# design.net
KiCad netlist of a schematic drawn in Altium Designer
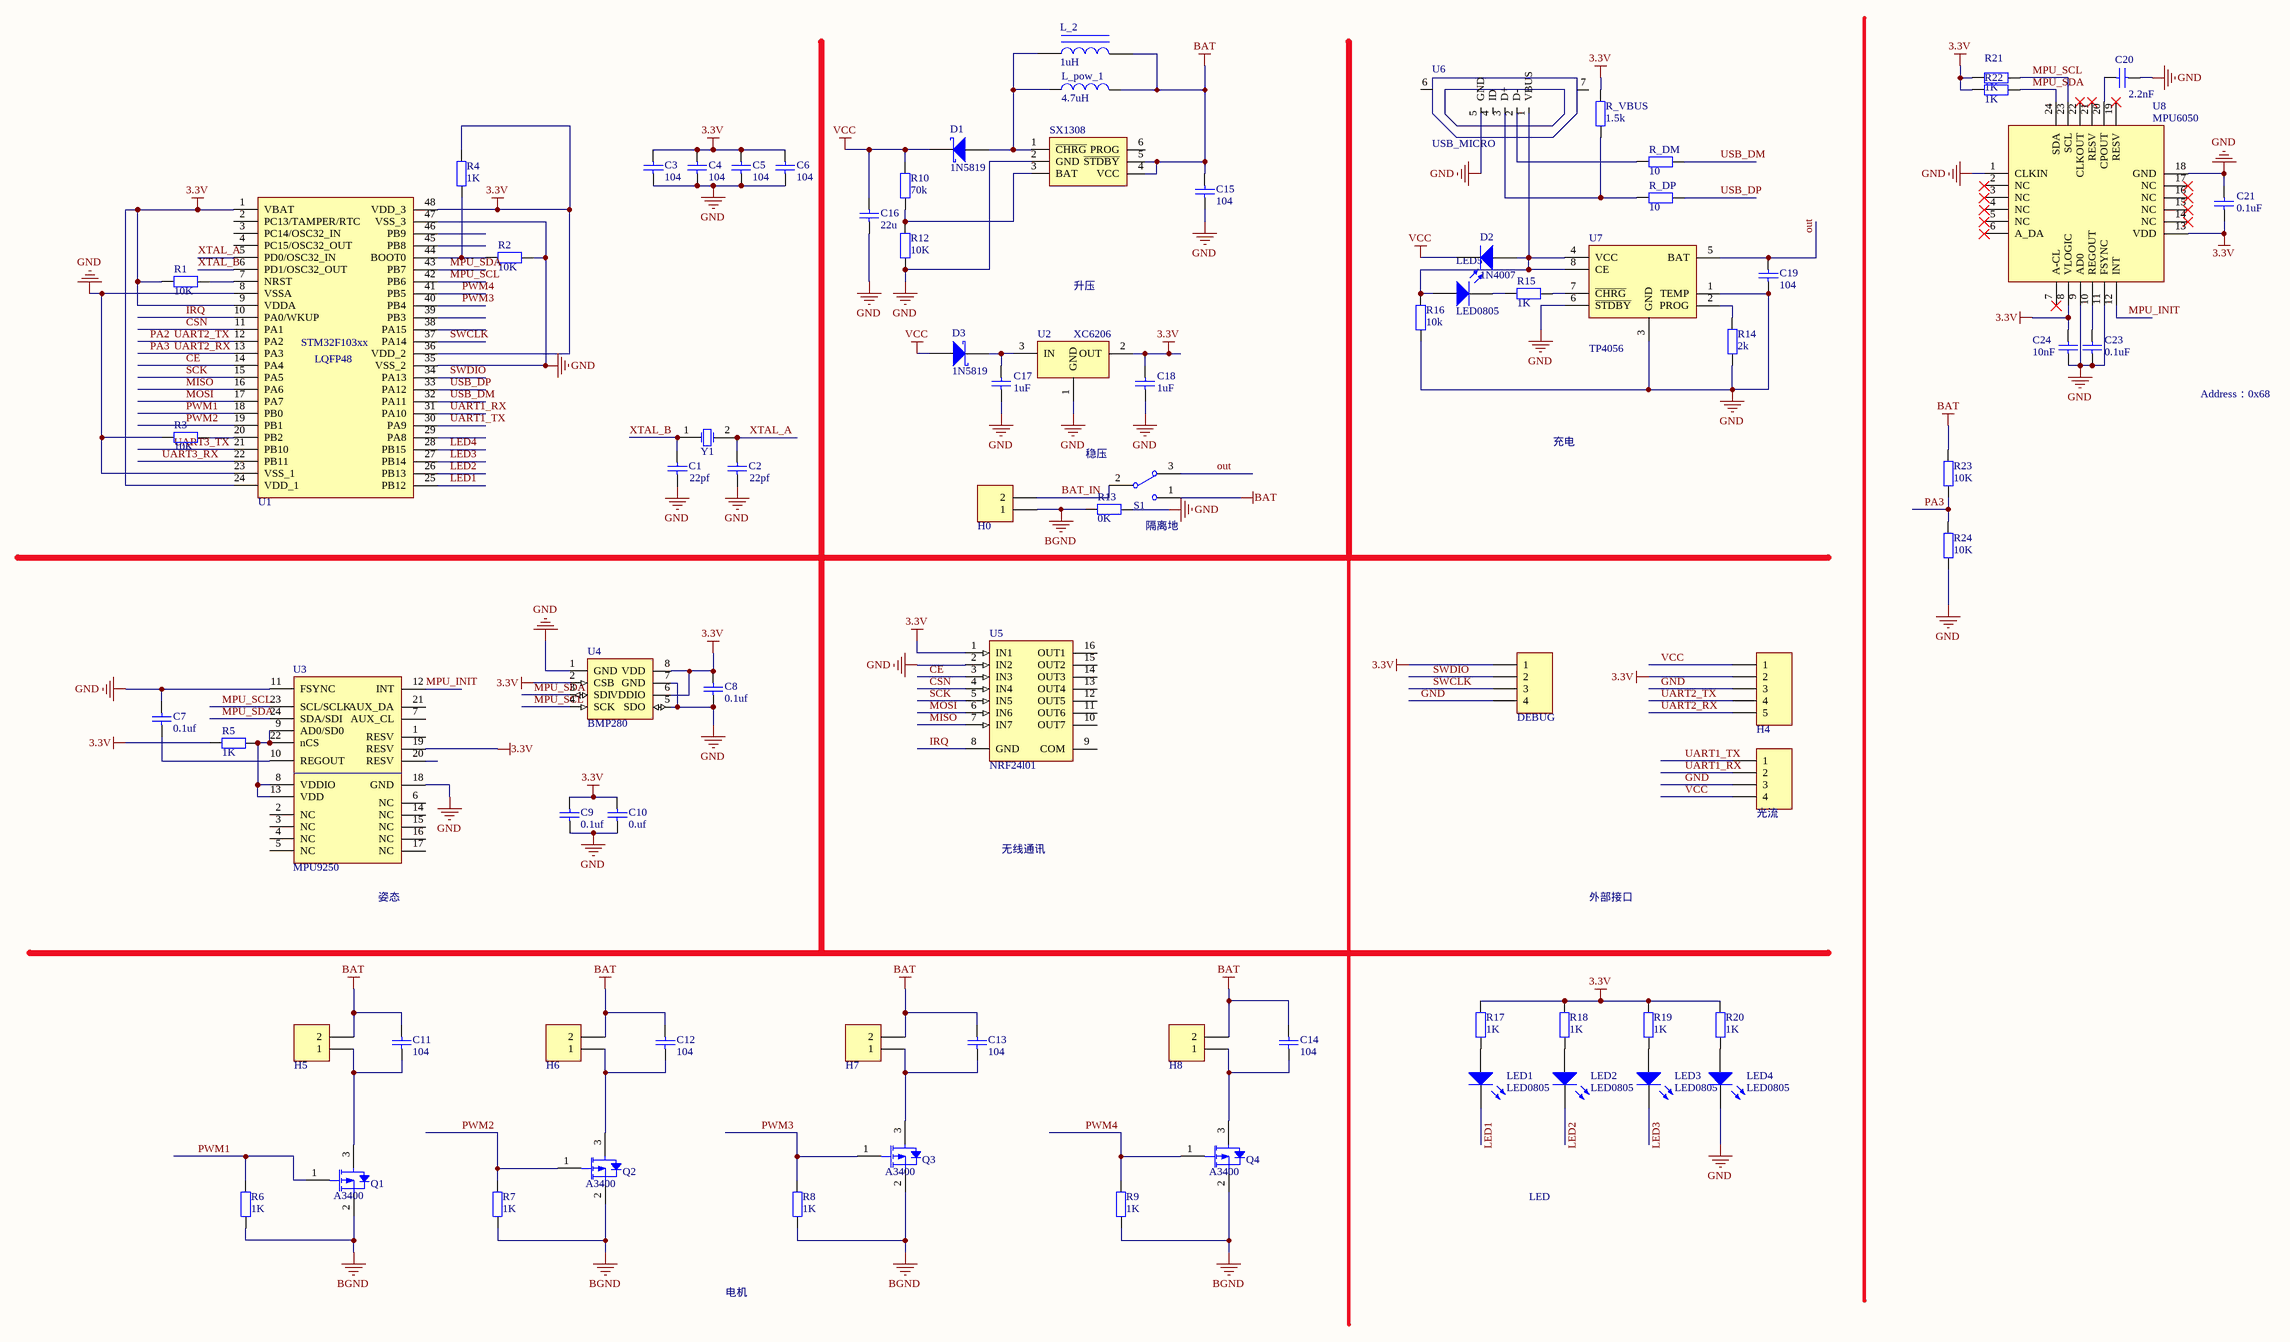
[diagram p0: 小四轴.SchDoc]

(export (version "E")
  (design (tool "Eeschema 10.0.6"))
  (components
    (comp (ref "C1")
      (value "22")
      (footprint "0603C")
      (description "0603瓷片电容")
      (fields (field (name "ALTIUM_UNNAMED_1") "22pf"))
      (libsource (lib "0.电阻电容电感") (part "Cap_0603"))
    )
    (comp (ref "C2")
      (value "104")
      (footprint "0603C")
      (description "0603瓷片电容")
      (fields (field (name "ALTIUM_UNNAMED_1") "22pf"))
      (libsource (lib "0.电阻电容电感") (part "Cap_0603"))
    )
    (comp (ref "C3")
      (value "104")
      (footprint "0603C")
      (description "0603瓷片电容")
      (libsource (lib "0.电阻电容电感") (part "Cap_0603"))
    )
    (comp (ref "C4")
      (value "104")
      (footprint "0603C")
      (description "0603瓷片电容")
      (libsource (lib "0.电阻电容电感") (part "Cap_0603"))
    )
    (comp (ref "C5")
      (value "104")
      (footprint "0603C")
      (description "0603瓷片电容")
      (libsource (lib "0.电阻电容电感") (part "Cap_0603"))
    )
    (comp (ref "C6")
      (value "104")
      (footprint "0603C")
      (description "0603瓷片电容")
      (libsource (lib "0.电阻电容电感") (part "Cap_0603"))
    )
    (comp (ref "C7")
      (value "0.1uf")
      (footprint "0603C")
      (description "0603瓷片电容")
      (libsource (lib "0.电阻电容电感") (part "Cap_0603"))
    )
    (comp (ref "C8")
      (value "0.1uf")
      (footprint "0603C")
      (description "0603瓷片电容")
      (libsource (lib "0.电阻电容电感") (part "Cap_0603"))
    )
    (comp (ref "C9")
      (value "0.1uf")
      (footprint "0603C")
      (description "0603瓷片电容")
      (libsource (lib "0.电阻电容电感") (part "Cap_0603"))
    )
    (comp (ref "C10")
      (value "0.uf")
      (footprint "0603C")
      (description "0603瓷片电容")
      (libsource (lib "0.电阻电容电感") (part "Cap_0603"))
    )
    (comp (ref "C11")
      (value "104")
      (footprint "0603C")
      (description "0603瓷片电容")
      (libsource (lib "0.电阻电容电感") (part "Cap_0603"))
    )
    (comp (ref "C12")
      (value "104")
      (footprint "0603C")
      (description "0603瓷片电容")
      (libsource (lib "0.电阻电容电感") (part "Cap_0603"))
    )
    (comp (ref "C13")
      (value "104")
      (footprint "0603C")
      (description "0603瓷片电容")
      (libsource (lib "0.电阻电容电感") (part "Cap_0603"))
    )
    (comp (ref "C14")
      (value "104")
      (footprint "0603C")
      (description "0603瓷片电容")
      (libsource (lib "0.电阻电容电感") (part "Cap_0603"))
    )
    (comp (ref "C15")
      (value "104")
      (footprint "0603C")
      (description "0603瓷片电容")
      (libsource (lib "0.电阻电容电感") (part "Cap_0603"))
    )
    (comp (ref "C16")
      (value "22u")
      (footprint "0603C")
      (description "0603瓷片电容")
      (libsource (lib "0.电阻电容电感") (part "Cap_0603"))
    )
    (comp (ref "C17")
      (value "1uF")
      (footprint "C_0603")
      (fields (field (name "Comment") "C_0603") (field (name "PUBLISHER") "Altium Limited"))
      (libsource (lib "RoboFly") (part "C_0603"))
    )
    (comp (ref "C18")
      (value "1uF")
      (footprint "C_0603")
      (fields (field (name "Comment") "C_0603") (field (name "PUBLISHER") "Altium Limited"))
      (libsource (lib "RoboFly") (part "C_0603"))
    )
    (comp (ref "C19")
      (value "104")
      (footprint "0603C")
      (description "0603瓷片电容")
      (libsource (lib "0.电阻电容电感") (part "Cap_0603"))
    )
    (comp (ref "C20")
      (value "2.2nF")
      (footprint "C_0603")
      (fields (field (name "Comment") "C_0603") (field (name "PUBLISHER") "Altium Limited"))
      (libsource (lib "RoboFly") (part "C_0603"))
    )
    (comp (ref "C21")
      (value "0.1uF")
      (footprint "C_0603")
      (fields (field (name "Comment") "C_0603") (field (name "PUBLISHER") "Altium Limited"))
      (libsource (lib "RoboFly") (part "C_0603"))
    )
    (comp (ref "C23")
      (value "0.1uF")
      (footprint "C_0603")
      (fields (field (name "Comment") "C_0603") (field (name "PUBLISHER") "Altium Limited"))
      (libsource (lib "RoboFly") (part "C_0603"))
    )
    (comp (ref "C24")
      (value "10nF")
      (footprint "C_0603")
      (fields (field (name "Comment") "C_0603") (field (name "PUBLISHER") "Altium Limited"))
      (libsource (lib "RoboFly") (part "C_0603"))
    )
    (comp (ref "D1")
      (value "1N5819")
      (footprint "DO214AC_SMA")
      (description "贴片肖特基二极管")
      (libsource (lib "1.二极管") (part "1N5817-5819SMD"))
    )
    (comp (ref "D2")
      (value "1N4007")
      (footprint "DO214AC_SMA")
      (description "贴片整流二极管")
      (libsource (lib "1.二极管") (part "1N4001-4007SMD"))
    )
    (comp (ref "D3")
      (value "1N5819")
      (footprint "DO214AC_SMA")
      (description "贴片肖特基二极管")
      (libsource (lib "1.二极管") (part "1N5817-5819SMD"))
    )
    (comp (ref "H0")
      (value "Header 2")
      (footprint "HDR1X2")
      (description "Header, 2-Pin")
      (fields (field (name "PUBLISHER") "Altium Limited"))
      (libsource (lib "9.接插件 连接器") (part "Header 2"))
    )
    (comp (ref "H1")
      (value "DEBUG")
      (footprint "HDR1X4")
      (description "Header, 4-Pin")
      (fields (field (name "PUBLISHER") "Altium Limited"))
      (libsource (lib "9.接插件 连接器") (part "Header 4"))
    )
    (comp (ref "H3")
      (value "光流")
      (footprint "HDR1X4")
      (description "Header, 4-Pin")
      (fields (field (name "PUBLISHER") "Altium Limited"))
      (libsource (lib "9.接插件 连接器") (part "Header 4"))
    )
    (comp (ref "H4")
      (value "Header 5")
      (footprint "HDR1X5")
      (description "Header, 5-Pin")
      (fields (field (name "PUBLISHER") "Altium Limited"))
      (libsource (lib "9.接插件 连接器") (part "Header 5"))
    )
    (comp (ref "H5")
      (value "Header 2")
      (footprint "HDR1X2")
      (description "Header, 2-Pin")
      (fields (field (name "PUBLISHER") "Altium Limited"))
      (libsource (lib "9.接插件 连接器") (part "Header 2"))
    )
    (comp (ref "H6")
      (value "Header 2")
      (footprint "HDR1X2")
      (description "Header, 2-Pin")
      (fields (field (name "PUBLISHER") "Altium Limited"))
      (libsource (lib "9.接插件 连接器") (part "Header 2"))
    )
    (comp (ref "H7")
      (value "Header 2")
      (footprint "HDR1X2")
      (description "Header, 2-Pin")
      (fields (field (name "PUBLISHER") "Altium Limited"))
      (libsource (lib "9.接插件 连接器") (part "Header 2"))
    )
    (comp (ref "H8")
      (value "Header 2")
      (footprint "HDR1X2")
      (description "Header, 2-Pin")
      (fields (field (name "PUBLISHER") "Altium Limited"))
      (libsource (lib "9.接插件 连接器") (part "Header 2"))
    )
    (comp (ref "LED1") (value "LED0805") (footprint "LED-0805") (libsource (lib "1.二极管") (part "LED0805")))
    (comp (ref "LED2") (value "LED0805") (footprint "LED-0805") (libsource (lib "1.二极管") (part "LED0805")))
    (comp (ref "LED3") (value "LED0805") (footprint "LED-0805") (libsource (lib "1.二极管") (part "LED0805")))
    (comp (ref "LED4") (value "LED0805") (footprint "LED-0805") (libsource (lib "1.二极管") (part "LED0805")))
    (comp (ref "LED5") (value "LED0805") (footprint "LED-0805") (libsource (lib "1.二极管") (part "LED0805")))
    (comp (ref "L_2")
      (value "1uH")
      (footprint "IND5X4")
      (description "IND5X4")
      (libsource (lib "0.电阻电容电感") (part "L_IND5X4"))
    )
    (comp (ref "L_pow_1")
      (value "4.7uH")
      (footprint "0805L")
      (description "0805贴片电感")
      (libsource (lib "0.电阻电容电感") (part "L_0805"))
    )
    (comp (ref "Q1")
      (value "A3400")
      (footprint "SOT23")
      (description "P沟道增强型场效应管")
      (libsource (lib "2.晶体管") (part "P-MOS_SOT23"))
    )
    (comp (ref "Q2")
      (value "A3400")
      (footprint "SOT23")
      (description "P沟道增强型场效应管")
      (libsource (lib "2.晶体管") (part "P-MOS_SOT23"))
    )
    (comp (ref "Q3")
      (value "A3400")
      (footprint "SOT23")
      (description "P沟道增强型场效应管")
      (libsource (lib "2.晶体管") (part "P-MOS_SOT23"))
    )
    (comp (ref "Q4")
      (value "A3400")
      (footprint "SOT23")
      (description "P沟道增强型场效应管")
      (libsource (lib "2.晶体管") (part "P-MOS_SOT23"))
    )
    (comp (ref "R1")
      (value "10K")
      (footprint "0603R")
      (description "0603贴片电阻")
      (libsource (lib "0.电阻电容电感") (part "Res_0603"))
    )
    (comp (ref "R2")
      (value "10K")
      (footprint "0603R")
      (description "0603贴片电阻")
      (libsource (lib "0.电阻电容电感") (part "Res_0603"))
    )
    (comp (ref "R3")
      (value "10K")
      (footprint "0603R")
      (description "0603贴片电阻")
      (libsource (lib "0.电阻电容电感") (part "Res_0603"))
    )
    (comp (ref "R4")
      (value "1K")
      (footprint "0603R")
      (description "0603贴片电阻")
      (libsource (lib "") (part "Res_0603_1"))
    )
    (comp (ref "R5")
      (value "1K")
      (footprint "0603R")
      (description "0603贴片电阻")
      (libsource (lib "") (part "Res_0603_2"))
    )
    (comp (ref "R6")
      (value "1K")
      (footprint "0603R")
      (description "0603贴片电阻")
      (libsource (lib "") (part "Res_0603_3"))
    )
    (comp (ref "R7")
      (value "1K")
      (footprint "0603R")
      (description "0603贴片电阻")
      (libsource (lib "") (part "Res_0603_3"))
    )
    (comp (ref "R8")
      (value "1K")
      (footprint "0603R")
      (description "0603贴片电阻")
      (libsource (lib "") (part "Res_0603_3"))
    )
    (comp (ref "R9")
      (value "1K")
      (footprint "0603R")
      (description "0603贴片电阻")
      (libsource (lib "") (part "Res_0603_3"))
    )
    (comp (ref "R10")
      (value "70k")
      (footprint "0603R")
      (description "0603贴片电阻")
      (libsource (lib "") (part "Res_0603_1"))
    )
    (comp (ref "R12")
      (value "10K")
      (footprint "0603R")
      (description "0603贴片电阻")
      (libsource (lib "") (part "Res_0603_1"))
    )
    (comp (ref "R13")
      (value "0K")
      (footprint "0603R")
      (description "0603贴片电阻")
      (libsource (lib "0.电阻电容电感") (part "Res_0603"))
    )
    (comp (ref "R14")
      (value "2k")
      (footprint "0603R")
      (description "0603贴片电阻")
      (libsource (lib "") (part "Res_0603_3"))
    )
    (comp (ref "R15")
      (value "1K")
      (footprint "0603R")
      (description "0603贴片电阻")
      (libsource (lib "") (part "Res_0603_2"))
    )
    (comp (ref "R16")
      (value "10k")
      (footprint "0603R")
      (description "0603贴片电阻")
      (libsource (lib "") (part "Res_0603_3"))
    )
    (comp (ref "R17")
      (value "1K")
      (footprint "0805R")
      (description "0805贴片电阻")
      (libsource (lib "0.电阻电容电感") (part "Res_0805"))
    )
    (comp (ref "R18")
      (value "1K")
      (footprint "0805R")
      (description "0805贴片电阻")
      (libsource (lib "0.电阻电容电感") (part "Res_0805"))
    )
    (comp (ref "R19")
      (value "1K")
      (footprint "0805R")
      (description "0805贴片电阻")
      (libsource (lib "0.电阻电容电感") (part "Res_0805"))
    )
    (comp (ref "R20")
      (value "1K")
      (footprint "0805R")
      (description "0805贴片电阻")
      (libsource (lib "0.电阻电容电感") (part "Res_0805"))
    )
    (comp (ref "R21")
      (value "1K")
      (footprint "0603R")
      (description "0603贴片电阻")
      (libsource (lib "") (part "Res_0603_2"))
    )
    (comp (ref "R22")
      (value "1K")
      (footprint "0603R")
      (description "0603贴片电阻")
      (libsource (lib "") (part "Res_0603_2"))
    )
    (comp (ref "R23")
      (value "10K")
      (footprint "0603R")
      (description "0603贴片电阻")
      (libsource (lib "") (part "Res_0603_3"))
    )
    (comp (ref "R24")
      (value "10K")
      (footprint "0603R")
      (description "0603贴片电阻")
      (libsource (lib "") (part "Res_0603_3"))
    )
    (comp (ref "R_DM")
      (value "10")
      (footprint "0603R")
      (description "0603贴片电阻")
      (libsource (lib "0.电阻电容电感") (part "Res_0603"))
    )
    (comp (ref "R_DP")
      (value "10")
      (footprint "0603R")
      (description "0603贴片电阻")
      (libsource (lib "0.电阻电容电感") (part "Res_0603"))
    )
    (comp (ref "R_VBUS")
      (value "1.5k")
      (footprint "0603R")
      (description "0603贴片电阻")
      (libsource (lib "") (part "Res_0603_1"))
    )
    (comp (ref "S1")
      (value "2档平拨开关 无支撑")
      (footprint "平拨2档开关100mil")
      (description "2.54mm脚距 无支撑")
      (libsource (lib "6.开关 按键") (part "2档平拨开关 无支撑"))
    )
    (comp (ref "SX1308") (value "TP4059") (footprint "SOT23-6S") (libsource (lib "MiniFly+") (part "TP4059")))
    (comp (ref "U1")
      (value "STM32F103C8T6")
      (footprint "LQFP48_M")
      (libsource (lib "7.MCU CPU") (part "STM32F103C8T6"))
    )
    (comp (ref "U2")
      (value "XC6206")
      (footprint "SOT-23(SOT-23-3)")
      (fields (field (name "PUBLISHER") "mazhongwei"))
      (libsource (lib "RoboFly") (part "XC6206"))
    )
    (comp (ref "U3") (value "MPU9250") (footprint "QFN24-0.4") (libsource (lib "MiniFly+") (part "MPU9250")))
    (comp (ref "U4") (value "BMP280") (footprint "LGA-8") (libsource (lib "MiniFly+") (part "BMP280")))
    (comp (ref "U5")
      (value "NRF24l01")
      (footprint "NSO16_M")
      (description "驱动芯片")
      (fields (field (name "PUBLISHER") "Altium Limited"))
      (libsource (lib "Fszhang") (part "ULN2003L"))
    )
    (comp (ref "U6")
      (value "USB_MICRO")
      (footprint "USB micro")
      (libsource (lib "9.接插件 连接器") (part "USB_MICRO"))
    )
    (comp (ref "U7")
      (value "TP4056")
      (footprint "SOP8")
      (description "锂电池充电管理芯片")
      (libsource (lib "5.电源器件") (part "TP4056"))
    )
    (comp (ref "U8")
      (value "MPU6050")
      (footprint "QFN-24_4x4x05P")
      (libsource (lib "RoboFly") (part "MPU6050"))
    )
    (comp (ref "Y1") (value "扁晶振") (footprint "Y-A-SMD") (libsource (lib "10.传感器 时钟") (part "XTAL1")))
  )
  (nets
    (net (code "1") (name "/BAT_IN") (class "Default")
      (node (ref "H0") (pin "2") (pinfunction "2_2") (pintype "passive"))
      (node (ref "S1") (pin "2") (pinfunction "2_2") (pintype "passive"))
    )
    (net (code "2") (name "/CE") (class "Default")
      (node (ref "U1") (pin "14") (pinfunction "PA4_14") (pintype "passive"))
      (node (ref "U5") (pin "3") (pinfunction "IN3_3") (pintype "input"))
    )
    (net (code "3") (name "/CSN") (class "Default")
      (node (ref "U1") (pin "11") (pinfunction "PA1_11") (pintype "passive"))
      (node (ref "U5") (pin "4") (pinfunction "IN4_4") (pintype "input"))
    )
    (net (code "4") (name "/IRQ") (class "Default")
      (node (ref "U1") (pin "10") (pinfunction "PA0/WKUP_10") (pintype "passive"))
      (node (ref "U5") (pin "8") (pinfunction "GND_8") (pintype "power_in"))
    )
    (net (code "5") (name "/LED1") (class "Default")
      (node (ref "LED1") (pin "2") (pinfunction "K_2") (pintype "passive"))
      (node (ref "U1") (pin "25") (pinfunction "PB12_25") (pintype "passive"))
    )
    (net (code "6") (name "/LED2") (class "Default")
      (node (ref "LED2") (pin "2") (pinfunction "K_2") (pintype "passive"))
      (node (ref "U1") (pin "26") (pinfunction "PB13_26") (pintype "passive"))
    )
    (net (code "7") (name "/LED3") (class "Default")
      (node (ref "LED3") (pin "2") (pinfunction "K_2") (pintype "passive"))
      (node (ref "U1") (pin "27") (pinfunction "PB14_27") (pintype "passive"))
    )
    (net (code "8") (name "/LED4") (class "Default")
      (node (ref "U1") (pin "28") (pinfunction "PB15_28") (pintype "passive"))
    )
    (net (code "9") (name "/MISO") (class "Default")
      (node (ref "U1") (pin "16") (pinfunction "PA6_16") (pintype "passive"))
      (node (ref "U5") (pin "7") (pinfunction "IN7_7") (pintype "input"))
    )
    (net (code "10") (name "/MOSI") (class "Default")
      (node (ref "U1") (pin "17") (pinfunction "PA7_17") (pintype "passive"))
      (node (ref "U5") (pin "6") (pinfunction "IN6_6") (pintype "input"))
    )
    (net (code "11") (name "/MPU_INIT") (class "Default")
      (node (ref "U3") (pin "12") (pinfunction "INT_12") (pintype "passive"))
      (node (ref "U8") (pin "12") (pinfunction "INT_12") (pintype "passive"))
    )
    (net (code "12") (name "/MPU_SCL") (class "Default")
      (node (ref "R21") (pin "2") (pinfunction "2_2") (pintype "passive"))
      (node (ref "U1") (pin "42") (pinfunction "PB6_42") (pintype "passive"))
      (node (ref "U3") (pin "23") (pinfunction "SCL/SCLK_23") (pintype "passive"))
      (node (ref "U4") (pin "4") (pinfunction "SCK_4") (pintype "input"))
      (node (ref "U8") (pin "23") (pinfunction "SCL_23") (pintype "passive"))
    )
    (net (code "13") (name "/MPU_SDA") (class "Default")
      (node (ref "R22") (pin "2") (pinfunction "2_2") (pintype "passive"))
      (node (ref "U1") (pin "43") (pinfunction "PB7_43") (pintype "passive"))
      (node (ref "U3") (pin "24") (pinfunction "SDA/SDI_24") (pintype "passive"))
      (node (ref "U4") (pin "3") (pinfunction "SDI_3") (pintype "bidirectional"))
      (node (ref "U8") (pin "24") (pinfunction "SDA_24") (pintype "passive"))
    )
    (net (code "14") (name "/PA2") (class "Default")
      (node (ref "H4") (pin "4") (pinfunction "4_4") (pintype "passive"))
      (node (ref "U1") (pin "12") (pinfunction "PA2_12") (pintype "passive"))
    )
    (net (code "15") (name "/PA3") (class "Default")
      (node (ref "H4") (pin "5") (pinfunction "5_5") (pintype "passive"))
      (node (ref "R23") (pin "1") (pinfunction "1_1") (pintype "passive"))
      (node (ref "R24") (pin "2") (pinfunction "2_2") (pintype "passive"))
      (node (ref "U1") (pin "13") (pinfunction "PA3_13") (pintype "passive"))
    )
    (net (code "16") (name "/PWM1") (class "Default")
      (node (ref "Q1") (pin "1") (pinfunction "G_1") (pintype "passive"))
      (node (ref "R6") (pin "2") (pinfunction "2_2") (pintype "passive"))
      (node (ref "U1") (pin "18") (pinfunction "PB0_18") (pintype "passive"))
    )
    (net (code "17") (name "/PWM2") (class "Default")
      (node (ref "Q2") (pin "1") (pinfunction "G_1") (pintype "passive"))
      (node (ref "R7") (pin "2") (pinfunction "2_2") (pintype "passive"))
      (node (ref "U1") (pin "19") (pinfunction "PB1_19") (pintype "passive"))
    )
    (net (code "18") (name "/PWM3") (class "Default")
      (node (ref "Q3") (pin "1") (pinfunction "G_1") (pintype "passive"))
      (node (ref "R8") (pin "2") (pinfunction "2_2") (pintype "passive"))
      (node (ref "U1") (pin "40") (pinfunction "PB4_40") (pintype "passive"))
    )
    (net (code "19") (name "/PWM4") (class "Default")
      (node (ref "Q4") (pin "1") (pinfunction "G_1") (pintype "passive"))
      (node (ref "R9") (pin "2") (pinfunction "2_2") (pintype "passive"))
      (node (ref "U1") (pin "41") (pinfunction "PB5_41") (pintype "passive"))
    )
    (net (code "20") (name "/SCK") (class "Default")
      (node (ref "U1") (pin "15") (pinfunction "PA5_15") (pintype "passive"))
      (node (ref "U5") (pin "5") (pinfunction "IN5_5") (pintype "input"))
    )
    (net (code "21") (name "/SWCLK") (class "Default")
      (node (ref "H1") (pin "3") (pinfunction "3_3") (pintype "passive"))
      (node (ref "U1") (pin "37") (pinfunction "PA14_37") (pintype "passive"))
    )
    (net (code "22") (name "/SWDIO") (class "Default")
      (node (ref "H1") (pin "2") (pinfunction "2_2") (pintype "passive"))
      (node (ref "U1") (pin "34") (pinfunction "PA13_34") (pintype "passive"))
    )
    (net (code "23") (name "/UART1_RX") (class "Default")
      (node (ref "H3") (pin "2") (pinfunction "2_2") (pintype "passive"))
      (node (ref "U1") (pin "31") (pinfunction "PA10_31") (pintype "passive"))
    )
    (net (code "24") (name "/UART1_TX") (class "Default")
      (node (ref "H3") (pin "1") (pinfunction "1_1") (pintype "passive"))
      (node (ref "U1") (pin "30") (pinfunction "PA9_30") (pintype "passive"))
    )
    (net (code "25") (name "/UART3_RX") (class "Default")
      (node (ref "U1") (pin "22") (pinfunction "PB11_22") (pintype "passive"))
    )
    (net (code "26") (name "/UART3_TX") (class "Default")
      (node (ref "U1") (pin "21") (pinfunction "PB10_21") (pintype "passive"))
    )
    (net (code "27") (name "/USB_DM") (class "Default")
      (node (ref "R_DM") (pin "1") (pinfunction "1_1") (pintype "passive"))
      (node (ref "U1") (pin "32") (pinfunction "PA11_32") (pintype "passive"))
    )
    (net (code "28") (name "/USB_DP") (class "Default")
      (node (ref "R_DP") (pin "1") (pinfunction "1_1") (pintype "passive"))
      (node (ref "U1") (pin "33") (pinfunction "PA12_33") (pintype "passive"))
    )
    (net (code "29") (name "/XTAL_A") (class "Default")
      (node (ref "C2") (pin "2") (pinfunction "2_2") (pintype "passive"))
      (node (ref "U1") (pin "5") (pinfunction "PD0/OSC32_IN_5") (pintype "passive"))
      (node (ref "Y1") (pin "2") (pinfunction "OSC2_2") (pintype "passive"))
    )
    (net (code "30") (name "/XTAL_B") (class "Default")
      (node (ref "C1") (pin "2") (pinfunction "2_2") (pintype "passive"))
      (node (ref "U1") (pin "6") (pinfunction "PD1/OSC32_OUT_6") (pintype "passive"))
      (node (ref "Y1") (pin "1") (pinfunction "OSC1_1") (pintype "passive"))
    )
    (net (code "31") (name "/out") (class "Default")
      (node (ref "C19") (pin "2") (pinfunction "2_2") (pintype "passive"))
      (node (ref "S1") (pin "3") (pinfunction "3_3") (pintype "passive"))
      (node (ref "U7") (pin "5") (pinfunction "BAT_5") (pintype "passive"))
    )
    (net (code "32") (name "3.3V") (class "Default")
      (node (ref "C10") (pin "2") (pinfunction "2_2") (pintype "passive"))
      (node (ref "C18") (pin "1") (pinfunction "1_1") (pintype "passive"))
      (node (ref "C21") (pin "2") (pinfunction "2_2") (pintype "passive"))
      (node (ref "C24") (pin "2") (pinfunction "2_2") (pintype "passive"))
      (node (ref "C3") (pin "2") (pinfunction "2_2") (pintype "passive"))
      (node (ref "C4") (pin "2") (pinfunction "2_2") (pintype "passive"))
      (node (ref "C5") (pin "2") (pinfunction "2_2") (pintype "passive"))
      (node (ref "C6") (pin "2") (pinfunction "2_2") (pintype "passive"))
      (node (ref "C8") (pin "2") (pinfunction "2_2") (pintype "passive"))
      (node (ref "C9") (pin "2") (pinfunction "2_2") (pintype "passive"))
      (node (ref "H1") (pin "1") (pinfunction "1_1") (pintype "passive"))
      (node (ref "H4") (pin "2") (pinfunction "2_2") (pintype "passive"))
      (node (ref "R1") (pin "2") (pinfunction "2_2") (pintype "passive"))
      (node (ref "R17") (pin "2") (pinfunction "2_2") (pintype "passive"))
      (node (ref "R18") (pin "2") (pinfunction "2_2") (pintype "passive"))
      (node (ref "R19") (pin "2") (pinfunction "2_2") (pintype "passive"))
      (node (ref "R20") (pin "2") (pinfunction "2_2") (pintype "passive"))
      (node (ref "R21") (pin "1") (pinfunction "1_1") (pintype "passive"))
      (node (ref "R22") (pin "1") (pinfunction "1_1") (pintype "passive"))
      (node (ref "R4") (pin "1") (pinfunction "1_1") (pintype "passive"))
      (node (ref "R5") (pin "1") (pinfunction "1_1") (pintype "passive"))
      (node (ref "R_VBUS") (pin "1") (pinfunction "1_1") (pintype "passive"))
      (node (ref "U1") (pin "1") (pinfunction "VBAT_1") (pintype "passive"))
      (node (ref "U1") (pin "24") (pinfunction "VDD_1_24") (pintype "passive"))
      (node (ref "U1") (pin "36") (pinfunction "VDD_2_36") (pintype "passive"))
      (node (ref "U1") (pin "48") (pinfunction "VDD_3_48") (pintype "passive"))
      (node (ref "U1") (pin "9") (pinfunction "VDDA_9") (pintype "passive"))
      (node (ref "U2") (pin "2") (pinfunction "OUT_2") (pintype "passive"))
      (node (ref "U3") (pin "19") (pinfunction "RESV_19") (pintype "passive"))
      (node (ref "U4") (pin "2") (pinfunction "CSB_2") (pintype "input"))
      (node (ref "U4") (pin "6") (pinfunction "VDDIO_6") (pintype "power_in"))
      (node (ref "U4") (pin "8") (pinfunction "VDD_8") (pintype "power_in"))
      (node (ref "U5") (pin "1") (pinfunction "IN1_1") (pintype "input"))
      (node (ref "U8") (pin "13") (pinfunction "VDD_13") (pintype "passive"))
      (node (ref "U8") (pin "8") (pinfunction "VLOGIC_8") (pintype "passive"))
    )
    (net (code "33") (name "BAT") (class "Default")
      (node (ref "C11") (pin "2") (pinfunction "2_2") (pintype "passive"))
      (node (ref "C12") (pin "2") (pinfunction "2_2") (pintype "passive"))
      (node (ref "C13") (pin "2") (pinfunction "2_2") (pintype "passive"))
      (node (ref "C14") (pin "2") (pinfunction "2_2") (pintype "passive"))
      (node (ref "C15") (pin "2") (pinfunction "2_2") (pintype "passive"))
      (node (ref "H5") (pin "2") (pinfunction "2_2") (pintype "passive"))
      (node (ref "H6") (pin "2") (pinfunction "2_2") (pintype "passive"))
      (node (ref "H7") (pin "2") (pinfunction "2_2") (pintype "passive"))
      (node (ref "H8") (pin "2") (pinfunction "2_2") (pintype "passive"))
      (node (ref "L_2") (pin "2") (pinfunction "2_2") (pintype "passive"))
      (node (ref "L_pow_1") (pin "2") (pinfunction "2_2") (pintype "passive"))
      (node (ref "R23") (pin "2") (pinfunction "2_2") (pintype "passive"))
      (node (ref "S1") (pin "1") (pinfunction "1_1") (pintype "passive"))
      (node (ref "SX1308") (pin "4") (pinfunction "VCC_4") (pintype "passive"))
      (node (ref "SX1308") (pin "5") (pinfunction "~{STDBY}_5") (pintype "passive"))
    )
    (net (code "34") (name "BGND") (class "Default")
      (node (ref "H0") (pin "1") (pinfunction "1_1") (pintype "passive"))
      (node (ref "Q1") (pin "2") (pinfunction "S_2") (pintype "passive"))
      (node (ref "Q2") (pin "2") (pinfunction "S_2") (pintype "passive"))
      (node (ref "Q3") (pin "2") (pinfunction "S_2") (pintype "passive"))
      (node (ref "Q4") (pin "2") (pinfunction "S_2") (pintype "passive"))
      (node (ref "R13") (pin "2") (pinfunction "2_2") (pintype "passive"))
      (node (ref "R6") (pin "1") (pinfunction "1_1") (pintype "passive"))
      (node (ref "R7") (pin "1") (pinfunction "1_1") (pintype "passive"))
      (node (ref "R8") (pin "1") (pinfunction "1_1") (pintype "passive"))
      (node (ref "R9") (pin "1") (pinfunction "1_1") (pintype "passive"))
    )
    (net (code "35") (name "GND") (class "Default")
      (node (ref "C1") (pin "1") (pinfunction "1_1") (pintype "passive"))
      (node (ref "C10") (pin "1") (pinfunction "1_1") (pintype "passive"))
      (node (ref "C15") (pin "1") (pinfunction "1_1") (pintype "passive"))
      (node (ref "C16") (pin "1") (pinfunction "1_1") (pintype "passive"))
      (node (ref "C17") (pin "2") (pinfunction "2_2") (pintype "passive"))
      (node (ref "C18") (pin "2") (pinfunction "2_2") (pintype "passive"))
      (node (ref "C19") (pin "1") (pinfunction "1_1") (pintype "passive"))
      (node (ref "C2") (pin "1") (pinfunction "1_1") (pintype "passive"))
      (node (ref "C20") (pin "1") (pinfunction "1_1") (pintype "passive"))
      (node (ref "C21") (pin "1") (pinfunction "1_1") (pintype "passive"))
      (node (ref "C23") (pin "2") (pinfunction "2_2") (pintype "passive"))
      (node (ref "C24") (pin "1") (pinfunction "1_1") (pintype "passive"))
      (node (ref "C3") (pin "1") (pinfunction "1_1") (pintype "passive"))
      (node (ref "C4") (pin "1") (pinfunction "1_1") (pintype "passive"))
      (node (ref "C5") (pin "1") (pinfunction "1_1") (pintype "passive"))
      (node (ref "C6") (pin "1") (pinfunction "1_1") (pintype "passive"))
      (node (ref "C7") (pin "2") (pinfunction "2_2") (pintype "passive"))
      (node (ref "C8") (pin "1") (pinfunction "1_1") (pintype "passive"))
      (node (ref "C9") (pin "1") (pinfunction "1_1") (pintype "passive"))
      (node (ref "H1") (pin "4") (pinfunction "4_4") (pintype "passive"))
      (node (ref "H3") (pin "3") (pinfunction "3_3") (pintype "passive"))
      (node (ref "H4") (pin "3") (pinfunction "3_3") (pintype "passive"))
      (node (ref "LED4") (pin "2") (pinfunction "K_2") (pintype "passive"))
      (node (ref "R12") (pin "2") (pinfunction "2_2") (pintype "passive"))
      (node (ref "R13") (pin "1") (pinfunction "1_1") (pintype "passive"))
      (node (ref "R14") (pin "1") (pinfunction "1_1") (pintype "passive"))
      (node (ref "R16") (pin "1") (pinfunction "1_1") (pintype "passive"))
      (node (ref "R2") (pin "1") (pinfunction "1_1") (pintype "passive"))
      (node (ref "R24") (pin "1") (pinfunction "1_1") (pintype "passive"))
      (node (ref "R3") (pin "2") (pinfunction "2_2") (pintype "passive"))
      (node (ref "SX1308") (pin "2") (pinfunction "GND_2") (pintype "passive"))
      (node (ref "U1") (pin "23") (pinfunction "VSS_1_23") (pintype "passive"))
      (node (ref "U1") (pin "35") (pinfunction "VSS_2_35") (pintype "passive"))
      (node (ref "U1") (pin "47") (pinfunction "VSS_3_47") (pintype "passive"))
      (node (ref "U1") (pin "8") (pinfunction "VSSA_8") (pintype "passive"))
      (node (ref "U2") (pin "1") (pinfunction "GND_1") (pintype "passive"))
      (node (ref "U3") (pin "11") (pinfunction "FSYNC_11") (pintype "passive"))
      (node (ref "U3") (pin "18") (pinfunction "GND_18") (pintype "passive"))
      (node (ref "U4") (pin "1") (pinfunction "GND_1") (pintype "passive"))
      (node (ref "U4") (pin "5") (pinfunction "SDO_5") (pintype "bidirectional"))
      (node (ref "U4") (pin "7") (pinfunction "GND_7") (pintype "power_in"))
      (node (ref "U5") (pin "2") (pinfunction "IN2_2") (pintype "input"))
      (node (ref "U6") (pin "5") (pinfunction "GND_5") (pintype "passive"))
      (node (ref "U7") (pin "1") (pinfunction "TEMP_1") (pintype "passive"))
      (node (ref "U7") (pin "3") (pinfunction "GND_3") (pintype "passive"))
      (node (ref "U7") (pin "6") (pinfunction "~{STDBY}_6") (pintype "passive"))
      (node (ref "U8") (pin "1") (pinfunction "CLKIN_1") (pintype "passive"))
      (node (ref "U8") (pin "11") (pinfunction "FSYNC_11") (pintype "passive"))
      (node (ref "U8") (pin "18") (pinfunction "GND_18") (pintype "passive"))
      (node (ref "U8") (pin "9") (pinfunction "AD0_9") (pintype "passive"))
    )
    (net (code "36") (name "Net-(D1-A)") (class "Default")
      (node (ref "D1") (pin "1") (pinfunction "A_1") (pintype "passive"))
      (node (ref "L_2") (pin "1") (pinfunction "1_1") (pintype "passive"))
      (node (ref "L_pow_1") (pin "1") (pinfunction "1_1") (pintype "passive"))
      (node (ref "SX1308") (pin "1") (pinfunction "~{CHRG}_1") (pintype "passive"))
    )
    (net (code "37") (name "Net-(D2-A)") (class "Default")
      (node (ref "D2") (pin "1") (pinfunction "A_1") (pintype "passive"))
      (node (ref "LED5") (pin "1") (pinfunction "A_1") (pintype "passive"))
      (node (ref "R16") (pin "2") (pinfunction "2_2") (pintype "passive"))
      (node (ref "U6") (pin "1") (pinfunction "VBUS_1") (pintype "passive"))
      (node (ref "U7") (pin "4") (pinfunction "VCC_4") (pintype "passive"))
      (node (ref "U7") (pin "8") (pinfunction "CE_8") (pintype "passive"))
    )
    (net (code "38") (name "Net-(D3-K)") (class "Default")
      (node (ref "C17") (pin "1") (pinfunction "1_1") (pintype "passive"))
      (node (ref "D3") (pin "2") (pinfunction "K_2") (pintype "passive"))
      (node (ref "U2") (pin "3") (pinfunction "IN_3") (pintype "passive"))
    )
    (net (code "39") (name "Net-(LED1-A)") (class "Default")
      (node (ref "LED1") (pin "1") (pinfunction "A_1") (pintype "passive"))
      (node (ref "R17") (pin "1") (pinfunction "1_1") (pintype "passive"))
    )
    (net (code "40") (name "Net-(LED2-A)") (class "Default")
      (node (ref "LED2") (pin "1") (pinfunction "A_1") (pintype "passive"))
      (node (ref "R18") (pin "1") (pinfunction "1_1") (pintype "passive"))
    )
    (net (code "41") (name "Net-(LED3-A)") (class "Default")
      (node (ref "LED3") (pin "1") (pinfunction "A_1") (pintype "passive"))
      (node (ref "R19") (pin "1") (pinfunction "1_1") (pintype "passive"))
    )
    (net (code "42") (name "Net-(LED4-A)") (class "Default")
      (node (ref "LED4") (pin "1") (pinfunction "A_1") (pintype "passive"))
      (node (ref "R20") (pin "1") (pinfunction "1_1") (pintype "passive"))
    )
    (net (code "43") (name "Net-(LED5-K)") (class "Default")
      (node (ref "LED5") (pin "2") (pinfunction "K_2") (pintype "passive"))
      (node (ref "R15") (pin "1") (pinfunction "1_1") (pintype "passive"))
    )
    (net (code "44") (name "Net-(Q1-D)") (class "Default")
      (node (ref "C11") (pin "1") (pinfunction "1_1") (pintype "passive"))
      (node (ref "H5") (pin "1") (pinfunction "1_1") (pintype "passive"))
      (node (ref "Q1") (pin "3") (pinfunction "D_3") (pintype "passive"))
    )
    (net (code "45") (name "Net-(Q2-D)") (class "Default")
      (node (ref "C12") (pin "1") (pinfunction "1_1") (pintype "passive"))
      (node (ref "H6") (pin "1") (pinfunction "1_1") (pintype "passive"))
      (node (ref "Q2") (pin "3") (pinfunction "D_3") (pintype "passive"))
    )
    (net (code "46") (name "Net-(Q3-D)") (class "Default")
      (node (ref "C13") (pin "1") (pinfunction "1_1") (pintype "passive"))
      (node (ref "H7") (pin "1") (pinfunction "1_1") (pintype "passive"))
      (node (ref "Q3") (pin "3") (pinfunction "D_3") (pintype "passive"))
    )
    (net (code "47") (name "Net-(Q4-D)") (class "Default")
      (node (ref "C14") (pin "1") (pinfunction "1_1") (pintype "passive"))
      (node (ref "H8") (pin "1") (pinfunction "1_1") (pintype "passive"))
      (node (ref "Q4") (pin "3") (pinfunction "D_3") (pintype "passive"))
    )
    (net (code "48") (name "Net-(SX1308-BAT)") (class "Default")
      (node (ref "R10") (pin "2") (pinfunction "2_2") (pintype "passive"))
      (node (ref "R12") (pin "1") (pinfunction "1_1") (pintype "passive"))
      (node (ref "SX1308") (pin "3") (pinfunction "BAT_3") (pintype "passive"))
    )
    (net (code "49") (name "Net-(U1-BOOT0)") (class "Default")
      (node (ref "R2") (pin "2") (pinfunction "2_2") (pintype "passive"))
      (node (ref "R4") (pin "2") (pinfunction "2_2") (pintype "passive"))
      (node (ref "U1") (pin "44") (pinfunction "BOOT0_44") (pintype "passive"))
    )
    (net (code "50") (name "Net-(U1-NRST)") (class "Default")
      (node (ref "R1") (pin "1") (pinfunction "1_1") (pintype "passive"))
      (node (ref "U1") (pin "7") (pinfunction "NRST_7") (pintype "passive"))
    )
    (net (code "51") (name "Net-(U1-PB2)") (class "Default")
      (node (ref "R3") (pin "1") (pinfunction "1_1") (pintype "passive"))
      (node (ref "U1") (pin "20") (pinfunction "PB2_20") (pintype "passive"))
    )
    (net (code "52") (name "Net-(U3-AD0{slash}SD0)") (class "Default")
      (node (ref "R5") (pin "2") (pinfunction "2_2") (pintype "passive"))
      (node (ref "U3") (pin "13") (pinfunction "VDD_13") (pintype "passive"))
      (node (ref "U3") (pin "22") (pinfunction "nCS_22") (pintype "passive"))
      (node (ref "U3") (pin "8") (pinfunction "VDDIO_8") (pintype "passive"))
      (node (ref "U3") (pin "9") (pinfunction "AD0/SD0_9") (pintype "passive"))
    )
    (net (code "53") (name "Net-(U3-REGOUT)") (class "Default")
      (node (ref "C7") (pin "1") (pinfunction "1_1") (pintype "passive"))
      (node (ref "U3") (pin "10") (pinfunction "REGOUT_10") (pintype "passive"))
    )
    (net (code "54") (name "Net-(U6-D+)") (class "Default")
      (node (ref "R_DP") (pin "2") (pinfunction "2_2") (pintype "passive"))
      (node (ref "R_VBUS") (pin "2") (pinfunction "2_2") (pintype "passive"))
      (node (ref "U6") (pin "3") (pinfunction "D+_3") (pintype "passive"))
    )
    (net (code "55") (name "Net-(U6-D-)") (class "Default")
      (node (ref "R_DM") (pin "2") (pinfunction "2_2") (pintype "passive"))
      (node (ref "U6") (pin "2") (pinfunction "D-_2") (pintype "passive"))
    )
    (net (code "56") (name "Net-(U7-PROG)") (class "Default")
      (node (ref "R14") (pin "2") (pinfunction "2_2") (pintype "passive"))
      (node (ref "U7") (pin "2") (pinfunction "PROG_2") (pintype "passive"))
    )
    (net (code "57") (name "Net-(U7-~{CHRG})") (class "Default")
      (node (ref "R15") (pin "2") (pinfunction "2_2") (pintype "passive"))
      (node (ref "U7") (pin "7") (pinfunction "~{CHRG}_7") (pintype "passive"))
    )
    (net (code "58") (name "Net-(U8-CPOUT)") (class "Default")
      (node (ref "C20") (pin "2") (pinfunction "2_2") (pintype "passive"))
      (node (ref "U8") (pin "20") (pinfunction "CPOUT_20") (pintype "passive"))
    )
    (net (code "59") (name "Net-(U8-REGOUT)") (class "Default")
      (node (ref "C23") (pin "1") (pinfunction "1_1") (pintype "passive"))
      (node (ref "U8") (pin "10") (pinfunction "REGOUT_10") (pintype "passive"))
    )
    (net (code "60") (name "VCC") (class "Default")
      (node (ref "C16") (pin "2") (pinfunction "2_2") (pintype "passive"))
      (node (ref "D1") (pin "2") (pinfunction "K_2") (pintype "passive"))
      (node (ref "D2") (pin "2") (pinfunction "K_2") (pintype "passive"))
      (node (ref "D3") (pin "1") (pinfunction "A_1") (pintype "passive"))
      (node (ref "H3") (pin "4") (pinfunction "4_4") (pintype "passive"))
      (node (ref "H4") (pin "1") (pinfunction "1_1") (pintype "passive"))
      (node (ref "R10") (pin "1") (pinfunction "1_1") (pintype "passive"))
    )
    (net (code "61") (name "unconnected-(SX1308-PROG-Pad6)") (class "Default")
      (node (ref "SX1308") (pin "6") (pinfunction "PROG_6") (pintype "passive"))
    )
    (net (code "62") (name "unconnected-(U1-PA8-Pad29)") (class "Default")
      (node (ref "U1") (pin "29") (pinfunction "PA8_29") (pintype "passive"))
    )
    (net (code "63") (name "unconnected-(U1-PA15-Pad38)") (class "Default")
      (node (ref "U1") (pin "38") (pinfunction "PA15_38") (pintype "passive"))
    )
    (net (code "64") (name "unconnected-(U1-PB3-Pad39)") (class "Default")
      (node (ref "U1") (pin "39") (pinfunction "PB3_39") (pintype "passive"))
    )
    (net (code "65") (name "unconnected-(U1-PB8-Pad45)") (class "Default")
      (node (ref "U1") (pin "45") (pinfunction "PB8_45") (pintype "passive"))
    )
    (net (code "66") (name "unconnected-(U1-PB9-Pad46)") (class "Default")
      (node (ref "U1") (pin "46") (pinfunction "PB9_46") (pintype "passive"))
    )
    (net (code "67") (name "unconnected-(U1-PC13{slash}TAMPER{slash}RTC-Pad2)") (class "Default")
      (node (ref "U1") (pin "2") (pinfunction "PC13/TAMPER/RTC_2") (pintype "passive"))
    )
    (net (code "68") (name "unconnected-(U1-PC14{slash}OSC32_IN-Pad3)") (class "Default")
      (node (ref "U1") (pin "3") (pinfunction "PC14/OSC32_IN_3") (pintype "passive"))
    )
    (net (code "69") (name "unconnected-(U1-PC15{slash}OSC32_OUT-Pad4)") (class "Default")
      (node (ref "U1") (pin "4") (pinfunction "PC15/OSC32_OUT_4") (pintype "passive"))
    )
    (net (code "70") (name "unconnected-(U3-AUX_CL-Pad7)") (class "Default")
      (node (ref "U3") (pin "7") (pinfunction "AUX_CL_7") (pintype "passive"))
    )
    (net (code "71") (name "unconnected-(U3-AUX_DA-Pad21)") (class "Default")
      (node (ref "U3") (pin "21") (pinfunction "AUX_DA_21") (pintype "passive"))
    )
    (net (code "72") (name "unconnected-(U3-NC-Pad2)") (class "Default")
      (node (ref "U3") (pin "2") (pinfunction "NC_2") (pintype "passive"))
    )
    (net (code "73") (name "unconnected-(U3-NC-Pad3)") (class "Default")
      (node (ref "U3") (pin "3") (pinfunction "NC_3") (pintype "passive"))
    )
    (net (code "74") (name "unconnected-(U3-NC-Pad4)") (class "Default")
      (node (ref "U3") (pin "4") (pinfunction "NC_4") (pintype "passive"))
    )
    (net (code "75") (name "unconnected-(U3-NC-Pad5)") (class "Default")
      (node (ref "U3") (pin "5") (pinfunction "NC_5") (pintype "passive"))
    )
    (net (code "76") (name "unconnected-(U3-NC-Pad6)") (class "Default")
      (node (ref "U3") (pin "6") (pinfunction "NC_6") (pintype "passive"))
    )
    (net (code "77") (name "unconnected-(U3-NC-Pad14)") (class "Default")
      (node (ref "U3") (pin "14") (pinfunction "NC_14") (pintype "passive"))
    )
    (net (code "78") (name "unconnected-(U3-NC-Pad15)") (class "Default")
      (node (ref "U3") (pin "15") (pinfunction "NC_15") (pintype "passive"))
    )
    (net (code "79") (name "unconnected-(U3-NC-Pad16)") (class "Default")
      (node (ref "U3") (pin "16") (pinfunction "NC_16") (pintype "passive"))
    )
    (net (code "80") (name "unconnected-(U3-NC-Pad17)") (class "Default")
      (node (ref "U3") (pin "17") (pinfunction "NC_17") (pintype "passive"))
    )
    (net (code "81") (name "unconnected-(U3-RESV-Pad1)") (class "Default")
      (node (ref "U3") (pin "1") (pinfunction "RESV_1") (pintype "passive"))
    )
    (net (code "82") (name "unconnected-(U3-RESV-Pad20)") (class "Default")
      (node (ref "U3") (pin "20") (pinfunction "RESV_20") (pintype "passive"))
    )
    (net (code "83") (name "unconnected-(U5-COM-Pad9)") (class "Default")
      (node (ref "U5") (pin "9") (pinfunction "COM_9") (pintype "passive"))
    )
    (net (code "84") (name "unconnected-(U5-OUT1-Pad16)") (class "Default")
      (node (ref "U5") (pin "16") (pinfunction "OUT1_16") (pintype "open_collector"))
    )
    (net (code "85") (name "unconnected-(U5-OUT2-Pad15)") (class "Default")
      (node (ref "U5") (pin "15") (pinfunction "OUT2_15") (pintype "open_collector"))
    )
    (net (code "86") (name "unconnected-(U5-OUT3-Pad14)") (class "Default")
      (node (ref "U5") (pin "14") (pinfunction "OUT3_14") (pintype "open_collector"))
    )
    (net (code "87") (name "unconnected-(U5-OUT4-Pad13)") (class "Default")
      (node (ref "U5") (pin "13") (pinfunction "OUT4_13") (pintype "open_collector"))
    )
    (net (code "88") (name "unconnected-(U5-OUT5-Pad12)") (class "Default")
      (node (ref "U5") (pin "12") (pinfunction "OUT5_12") (pintype "open_collector"))
    )
    (net (code "89") (name "unconnected-(U5-OUT6-Pad11)") (class "Default")
      (node (ref "U5") (pin "11") (pinfunction "OUT6_11") (pintype "open_collector"))
    )
    (net (code "90") (name "unconnected-(U5-OUT7-Pad10)") (class "Default")
      (node (ref "U5") (pin "10") (pinfunction "OUT7_10") (pintype "open_collector"))
    )
    (net (code "91") (name "unconnected-(U6-ID-Pad4)") (class "Default")
      (node (ref "U6") (pin "4") (pinfunction "ID_4") (pintype "passive"))
    )
    (net (code "92") (name "unconnected-(U6-Pad6)") (class "Default")
      (node (ref "U6") (pin "6") (pintype "passive"))
    )
    (net (code "93") (name "unconnected-(U6-Pad7)") (class "Default")
      (node (ref "U6") (pin "7") (pintype "passive"))
    )
    (net (code "94") (name "unconnected-(U8-A-CL-Pad7)") (class "Default")
      (node (ref "U8") (pin "7") (pinfunction "A-CL_7") (pintype "passive+no_connect"))
    )
    (net (code "95") (name "unconnected-(U8-A_DA-Pad6)") (class "Default")
      (node (ref "U8") (pin "6") (pinfunction "A_DA_6") (pintype "passive+no_connect"))
    )
    (net (code "96") (name "unconnected-(U8-CLKOUT-Pad22)") (class "Default")
      (node (ref "U8") (pin "22") (pinfunction "CLKOUT_22") (pintype "passive+no_connect"))
    )
    (net (code "97") (name "unconnected-(U8-NC-Pad2)") (class "Default")
      (node (ref "U8") (pin "2") (pinfunction "NC_2") (pintype "passive+no_connect"))
    )
    (net (code "98") (name "unconnected-(U8-NC-Pad3)") (class "Default")
      (node (ref "U8") (pin "3") (pinfunction "NC_3") (pintype "passive+no_connect"))
    )
    (net (code "99") (name "unconnected-(U8-NC-Pad4)") (class "Default")
      (node (ref "U8") (pin "4") (pinfunction "NC_4") (pintype "passive+no_connect"))
    )
    (net (code "100") (name "unconnected-(U8-NC-Pad5)") (class "Default")
      (node (ref "U8") (pin "5") (pinfunction "NC_5") (pintype "passive+no_connect"))
    )
    (net (code "101") (name "unconnected-(U8-NC-Pad14)") (class "Default")
      (node (ref "U8") (pin "14") (pinfunction "NC_14") (pintype "passive+no_connect"))
    )
    (net (code "102") (name "unconnected-(U8-NC-Pad15)") (class "Default")
      (node (ref "U8") (pin "15") (pinfunction "NC_15") (pintype "passive+no_connect"))
    )
    (net (code "103") (name "unconnected-(U8-NC-Pad16)") (class "Default")
      (node (ref "U8") (pin "16") (pinfunction "NC_16") (pintype "passive+no_connect"))
    )
    (net (code "104") (name "unconnected-(U8-NC-Pad17)") (class "Default")
      (node (ref "U8") (pin "17") (pinfunction "NC_17") (pintype "passive+no_connect"))
    )
    (net (code "105") (name "unconnected-(U8-RESV-Pad19)") (class "Default")
      (node (ref "U8") (pin "19") (pinfunction "RESV_19") (pintype "passive+no_connect"))
    )
    (net (code "106") (name "unconnected-(U8-RESV-Pad21)") (class "Default")
      (node (ref "U8") (pin "21") (pinfunction "RESV_21") (pintype "passive+no_connect"))
    )
  )
)
